# mainboard.net
KiCad netlist of a schematic drawn in EAGLE
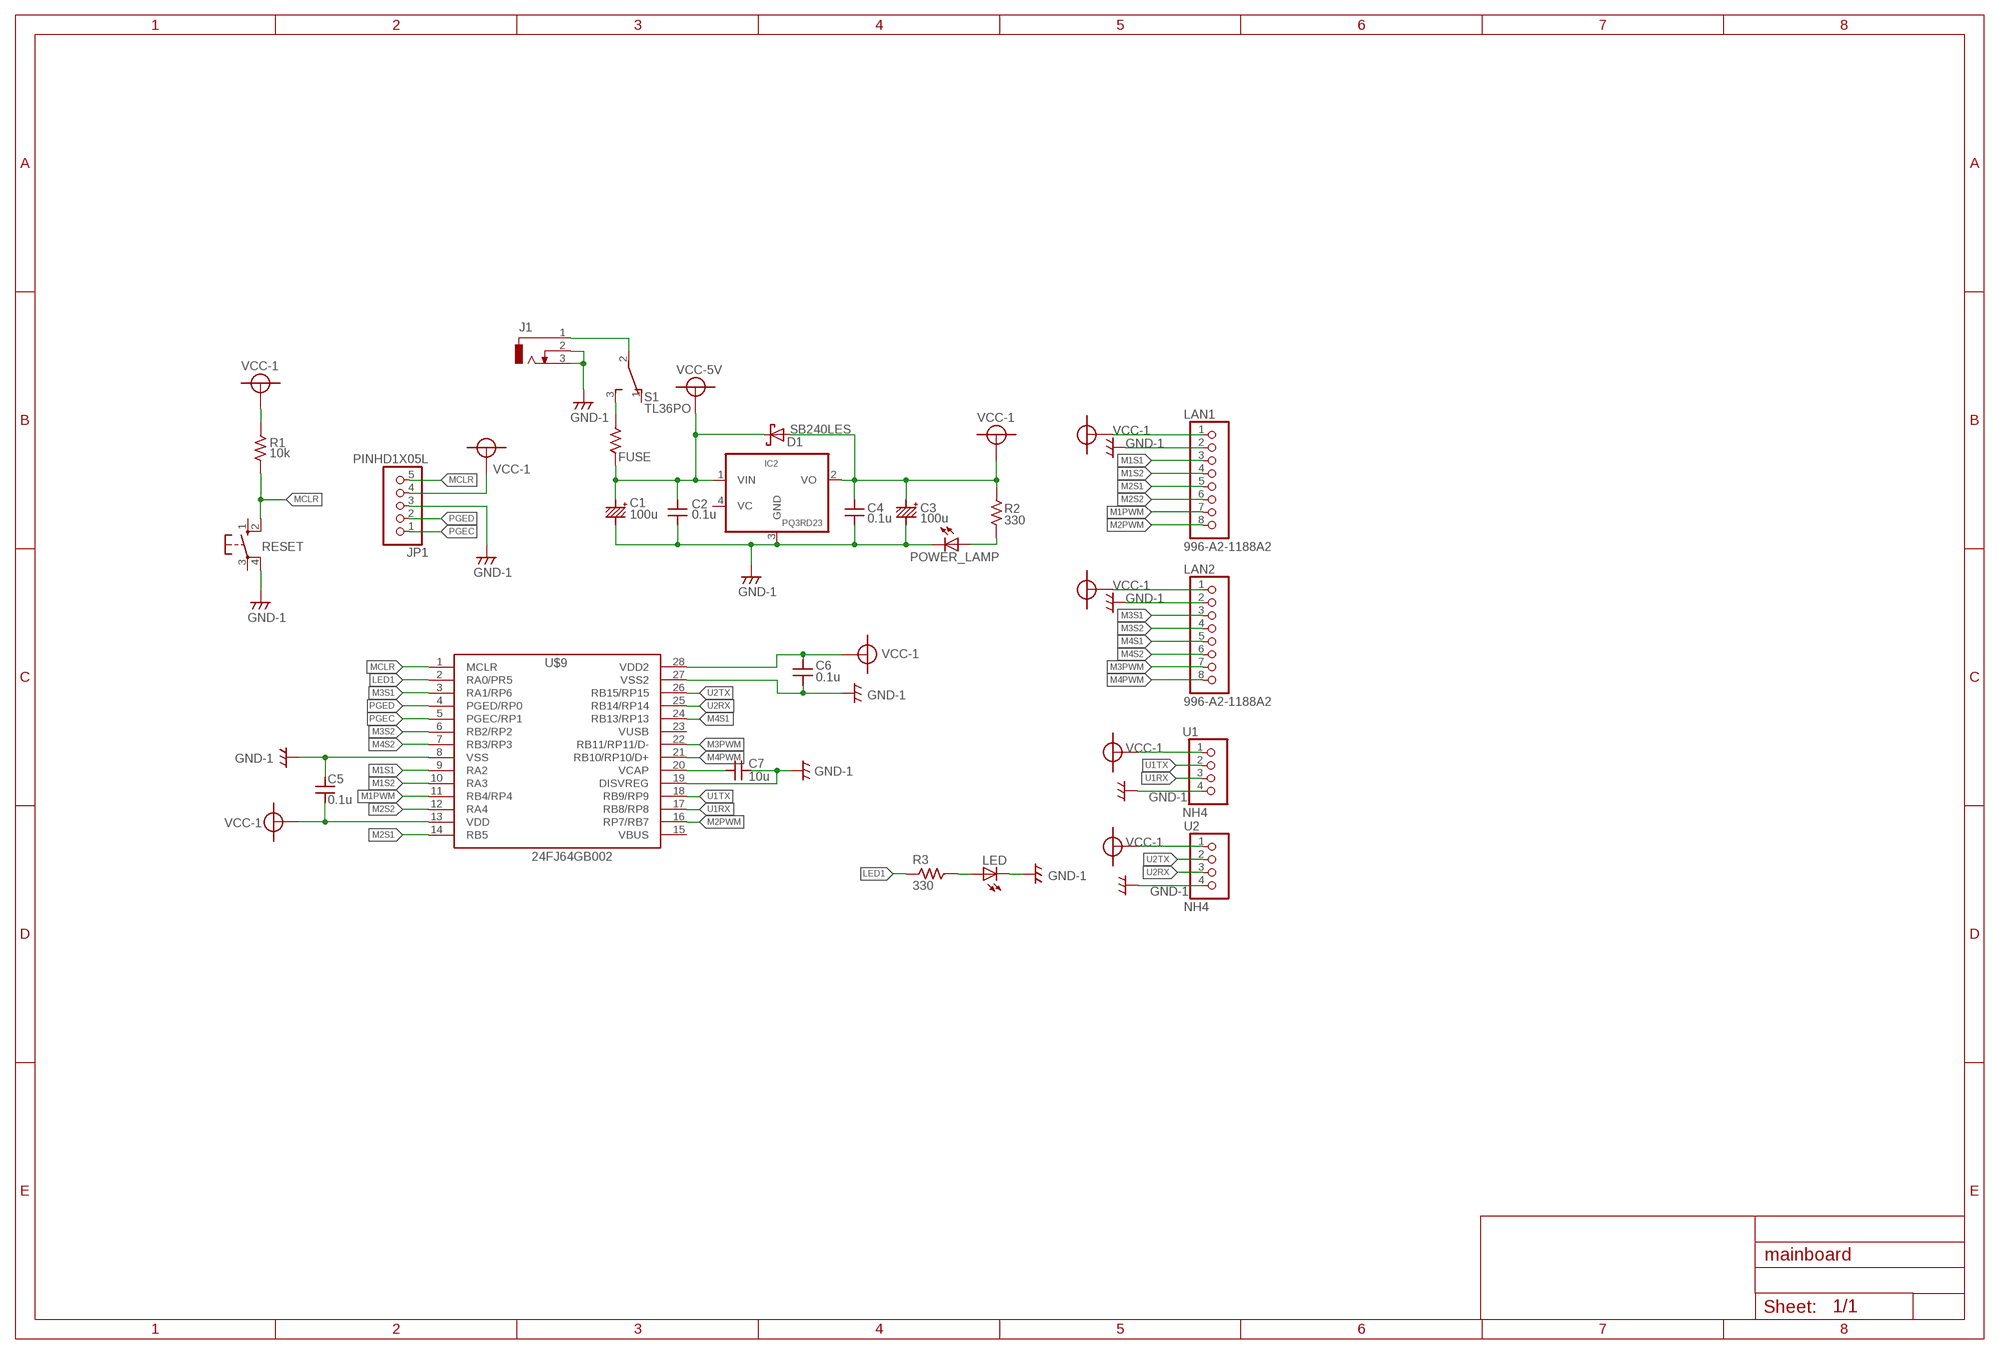
[diagram p0: schematic, sheet 1]

(export (version "E")
  (design (tool "Eeschema 10.0.6"))
  (components
    (comp (ref "C1")
      (value "100u")
      (footprint "eagle-import:CC_3")
      (libsource (lib "eagle-import") (part "C+25V100"))
    )
    (comp (ref "C2")
      (value "0.1u")
      (footprint "eagle-import:C_1")
      (libsource (lib "eagle-import") (part "CC2.54"))
    )
    (comp (ref "C3")
      (value "100u")
      (footprint "eagle-import:CC_3")
      (libsource (lib "eagle-import") (part "C+25V100"))
    )
    (comp (ref "C4")
      (value "0.1u")
      (footprint "eagle-import:C_1")
      (libsource (lib "eagle-import") (part "CC2.54"))
    )
    (comp (ref "C5")
      (value "0.1u")
      (footprint "eagle-import:C_1")
      (libsource (lib "eagle-import") (part "CC2.54"))
    )
    (comp (ref "C6")
      (value "0.1u")
      (footprint "eagle-import:C_1")
      (libsource (lib "eagle-import") (part "CC2.54"))
    )
    (comp (ref "C7")
      (value "10u")
      (footprint "eagle-import:C_1")
      (libsource (lib "eagle-import") (part "CC2.54"))
    )
    (comp (ref "D1")
      (value "SB240LES")
      (footprint "eagle-import:DO35-7")
      (libsource (lib "eagle-import") (part "SB240LES"))
    )
    (comp (ref "FUSE")
      (value "R3216(1206)")
      (footprint "eagle-import:C3216")
      (libsource (lib "eagle-import") (part "R3216(1206)"))
    )
    (comp (ref "IC2")
      (value "PQ3RD23")
      (footprint "eagle-import:TO220BV-4")
      (libsource (lib "eagle-import") (part "PQ3RD23"))
    )
    (comp (ref "J1")
      (value "DCJ0303")
      (footprint "eagle-import:DCJ0303")
      (libsource (lib "eagle-import") (part "DCJ0303"))
    )
    (comp (ref "JP1")
      (value "PINHD1X05L")
      (footprint "eagle-import:1X05L")
      (libsource (lib "eagle-import") (part "PINHD1X05L"))
    )
    (comp (ref "LAN1")
      (value "996-A2-1188A2")
      (footprint "eagle-import:996-A2-1188A2")
      (libsource (lib "eagle-import") (part "996-A2-1188A2"))
    )
    (comp (ref "LAN2")
      (value "996-A2-1188A2")
      (footprint "eagle-import:996-A2-1188A2")
      (libsource (lib "eagle-import") (part "996-A2-1188A2"))
    )
    (comp (ref "LED")
      (value "LED\"\"")
      (footprint "eagle-import:LED5MM")
      (libsource (lib "eagle-import") (part "LED{dblquote}{dblquote}"))
    )
    (comp (ref "POWER_LAMP")
      (value "LED\"\"")
      (footprint "eagle-import:LED5MM")
      (libsource (lib "eagle-import") (part "LED{dblquote}{dblquote}"))
    )
    (comp (ref "R1")
      (value "10k")
      (footprint "eagle-import:R_1_4W")
      (libsource (lib "eagle-import") (part "R1/4W"))
    )
    (comp (ref "R2")
      (value "330")
      (footprint "eagle-import:R_1_4W")
      (libsource (lib "eagle-import") (part "R1/4W"))
    )
    (comp (ref "R3")
      (value "330")
      (footprint "eagle-import:R_1_4W")
      (libsource (lib "eagle-import") (part "R1/4W"))
    )
    (comp (ref "RESET")
      (value "10-XX")
      (footprint "eagle-import:B3F-10XX")
      (fields (field (name "MPN") "B3F-1000"))
      (libsource (lib "eagle-import") (part "10-XX"))
    )
    (comp (ref "S1")
      (value "TL36PO")
      (footprint "eagle-import:TL3XPO")
      (libsource (lib "eagle-import") (part "TL36PO"))
    )
    (comp (ref "U$9")
      (value "24FJ64GB002")
      (footprint "eagle-import:DIL28-3")
      (libsource (lib "eagle-import") (part "24FJ64GB002"))
    )
    (comp (ref "U1")
      (value "NH4")
      (footprint "eagle-import:NH4")
      (libsource (lib "eagle-import") (part "NH4"))
    )
    (comp (ref "U2")
      (value "NH4")
      (footprint "eagle-import:NH4")
      (libsource (lib "eagle-import") (part "NH4"))
    )
  )
  (nets
    (net (code "1") (name "GND-1") (class "Default")
      (node (ref "C1") (pin "-") (pinfunction "P$2-_-") (pintype "passive"))
      (node (ref "C2") (pin "P$2") (pinfunction "P$2_P$2") (pintype "passive"))
      (node (ref "C3") (pin "-") (pinfunction "P$2-_-") (pintype "passive"))
      (node (ref "C4") (pin "P$2") (pinfunction "P$2_P$2") (pintype "passive"))
      (node (ref "C5") (pin "P$1") (pinfunction "P$1_P$1") (pintype "passive"))
      (node (ref "C6") (pin "P$2") (pinfunction "P$2_P$2") (pintype "passive"))
      (node (ref "C7") (pin "P$2") (pinfunction "P$2_P$2") (pintype "passive"))
      (node (ref "IC2") (pin "3") (pinfunction "GND_3") (pintype "bidirectional"))
      (node (ref "J1") (pin "2") (pinfunction "2_2") (pintype "passive"))
      (node (ref "J1") (pin "3") (pinfunction "3_3") (pintype "passive"))
      (node (ref "JP1") (pin "3") (pinfunction "P$3_3") (pintype "bidirectional"))
      (node (ref "LAN1") (pin "2") (pinfunction "P$2_2") (pintype "bidirectional"))
      (node (ref "LAN2") (pin "2") (pinfunction "P$2_2") (pintype "bidirectional"))
      (node (ref "LED") (pin "K") (pinfunction "C_K") (pintype "passive"))
      (node (ref "POWER_LAMP") (pin "K") (pinfunction "C_K") (pintype "passive"))
      (node (ref "RESET") (pin "4") (pinfunction "P1_4") (pintype "passive"))
      (node (ref "U$9") (pin "19") (pinfunction "DISVREG_19") (pintype "bidirectional"))
      (node (ref "U$9") (pin "27") (pinfunction "VSS2_27") (pintype "bidirectional"))
      (node (ref "U$9") (pin "8") (pinfunction "VSS_8") (pintype "bidirectional"))
      (node (ref "U1") (pin "4") (pinfunction "P$4_4") (pintype "bidirectional"))
      (node (ref "U2") (pin "4") (pinfunction "P$4_4") (pintype "bidirectional"))
    )
    (net (code "2") (name "LED1") (class "Default")
      (node (ref "R3") (pin "P$1") (pinfunction "P$1_P$1") (pintype "passive"))
      (node (ref "U$9") (pin "2") (pinfunction "RA0/PR5_2") (pintype "bidirectional"))
    )
    (net (code "3") (name "M1PWM") (class "Default")
      (node (ref "LAN1") (pin "7") (pinfunction "P$7_7") (pintype "bidirectional"))
      (node (ref "U$9") (pin "11") (pinfunction "RB4/RP4_11") (pintype "bidirectional"))
    )
    (net (code "4") (name "M1S1") (class "Default")
      (node (ref "LAN1") (pin "3") (pinfunction "P$3_3") (pintype "bidirectional"))
      (node (ref "U$9") (pin "9") (pinfunction "RA2_9") (pintype "bidirectional"))
    )
    (net (code "5") (name "M1S2") (class "Default")
      (node (ref "LAN1") (pin "4") (pinfunction "P$4_4") (pintype "bidirectional"))
      (node (ref "U$9") (pin "10") (pinfunction "RA3_10") (pintype "bidirectional"))
    )
    (net (code "6") (name "M2PWM") (class "Default")
      (node (ref "LAN1") (pin "8") (pinfunction "P$8_8") (pintype "bidirectional"))
      (node (ref "U$9") (pin "16") (pinfunction "RP7/RB7_16") (pintype "bidirectional"))
    )
    (net (code "7") (name "M2S1") (class "Default")
      (node (ref "LAN1") (pin "5") (pinfunction "P$5_5") (pintype "bidirectional"))
      (node (ref "U$9") (pin "14") (pinfunction "RB5_14") (pintype "bidirectional"))
    )
    (net (code "8") (name "M2S2") (class "Default")
      (node (ref "LAN1") (pin "6") (pinfunction "P$6_6") (pintype "bidirectional"))
      (node (ref "U$9") (pin "12") (pinfunction "RA4_12") (pintype "bidirectional"))
    )
    (net (code "9") (name "M3PWM") (class "Default")
      (node (ref "LAN2") (pin "7") (pinfunction "P$7_7") (pintype "bidirectional"))
      (node (ref "U$9") (pin "22") (pinfunction "RB11/RP11/D-_22") (pintype "bidirectional"))
    )
    (net (code "10") (name "M3S1") (class "Default")
      (node (ref "LAN2") (pin "3") (pinfunction "P$3_3") (pintype "bidirectional"))
      (node (ref "U$9") (pin "3") (pinfunction "RA1/RP6_3") (pintype "bidirectional"))
    )
    (net (code "11") (name "M3S2") (class "Default")
      (node (ref "LAN2") (pin "4") (pinfunction "P$4_4") (pintype "bidirectional"))
      (node (ref "U$9") (pin "6") (pinfunction "RB2/RP2_6") (pintype "bidirectional"))
    )
    (net (code "12") (name "M4PWM") (class "Default")
      (node (ref "LAN2") (pin "8") (pinfunction "P$8_8") (pintype "bidirectional"))
      (node (ref "U$9") (pin "21") (pinfunction "RB10/RP10/D+_21") (pintype "bidirectional"))
    )
    (net (code "13") (name "M4S1") (class "Default")
      (node (ref "LAN2") (pin "5") (pinfunction "P$5_5") (pintype "bidirectional"))
      (node (ref "U$9") (pin "24") (pinfunction "RB13/RP13_24") (pintype "bidirectional"))
    )
    (net (code "14") (name "M4S2") (class "Default")
      (node (ref "LAN2") (pin "6") (pinfunction "P$6_6") (pintype "bidirectional"))
      (node (ref "U$9") (pin "7") (pinfunction "RB3/RP3_7") (pintype "bidirectional"))
    )
    (net (code "15") (name "MCLR") (class "Default")
      (node (ref "JP1") (pin "5") (pinfunction "P$5_5") (pintype "bidirectional"))
      (node (ref "R1") (pin "P$1") (pinfunction "P$1_P$1") (pintype "passive"))
      (node (ref "RESET") (pin "2") (pinfunction "S1_2") (pintype "passive"))
      (node (ref "U$9") (pin "1") (pinfunction "MCLR_1") (pintype "bidirectional"))
    )
    (net (code "16") (name "Net-(FUSE-P$2)") (class "Default")
      (node (ref "FUSE") (pin "2") (pinfunction "P$2_2") (pintype "passive"))
      (node (ref "S1") (pin "3") (pinfunction "S_3") (pintype "passive"))
    )
    (net (code "17") (name "Net-(LED-PadA)") (class "Default")
      (node (ref "LED") (pin "A") (pinfunction "A_A") (pintype "passive"))
      (node (ref "R3") (pin "P$2") (pinfunction "P$2_P$2") (pintype "passive"))
    )
    (net (code "18") (name "Net-(POWER_LAMP-PadA)") (class "Default")
      (node (ref "POWER_LAMP") (pin "A") (pinfunction "A_A") (pintype "passive"))
      (node (ref "R2") (pin "P$1") (pinfunction "P$1_P$1") (pintype "passive"))
    )
    (net (code "19") (name "Net-(S1-P)") (class "Default")
      (node (ref "J1") (pin "1") (pinfunction "1_1") (pintype "passive"))
      (node (ref "S1") (pin "2") (pinfunction "P_2") (pintype "passive"))
    )
    (net (code "20") (name "Net-(U$9-VCAP)") (class "Default")
      (node (ref "C7") (pin "P$1") (pinfunction "P$1_P$1") (pintype "passive"))
      (node (ref "U$9") (pin "20") (pinfunction "VCAP_20") (pintype "bidirectional"))
    )
    (net (code "21") (name "PGEC") (class "Default")
      (node (ref "JP1") (pin "1") (pinfunction "P$1_1") (pintype "bidirectional"))
      (node (ref "U$9") (pin "5") (pinfunction "PGEC/RP1_5") (pintype "bidirectional"))
    )
    (net (code "22") (name "PGED") (class "Default")
      (node (ref "JP1") (pin "2") (pinfunction "P$2_2") (pintype "bidirectional"))
      (node (ref "U$9") (pin "4") (pinfunction "PGED/RP0_4") (pintype "bidirectional"))
    )
    (net (code "23") (name "U1RX") (class "Default")
      (node (ref "U$9") (pin "17") (pinfunction "RB8/RP8_17") (pintype "bidirectional"))
      (node (ref "U1") (pin "3") (pinfunction "P$3_3") (pintype "bidirectional"))
    )
    (net (code "24") (name "U1TX") (class "Default")
      (node (ref "U$9") (pin "18") (pinfunction "RB9/RP9_18") (pintype "bidirectional"))
      (node (ref "U1") (pin "2") (pinfunction "P$2_2") (pintype "bidirectional"))
    )
    (net (code "25") (name "U2RX") (class "Default")
      (node (ref "U$9") (pin "25") (pinfunction "RB14/RP14_25") (pintype "bidirectional"))
      (node (ref "U2") (pin "3") (pinfunction "P$3_3") (pintype "bidirectional"))
    )
    (net (code "26") (name "U2TX") (class "Default")
      (node (ref "U$9") (pin "26") (pinfunction "RB15/RP15_26") (pintype "bidirectional"))
      (node (ref "U2") (pin "2") (pinfunction "P$2_2") (pintype "bidirectional"))
    )
    (net (code "27") (name "VCC-1") (class "Default")
      (node (ref "C3") (pin "+") (pinfunction "P$1+_+") (pintype "passive"))
      (node (ref "C4") (pin "P$1") (pinfunction "P$1_P$1") (pintype "passive"))
      (node (ref "C5") (pin "P$2") (pinfunction "P$2_P$2") (pintype "passive"))
      (node (ref "C6") (pin "P$1") (pinfunction "P$1_P$1") (pintype "passive"))
      (node (ref "D1") (pin "A") (pinfunction "A_A") (pintype "passive"))
      (node (ref "IC2") (pin "2") (pinfunction "VO_2") (pintype "bidirectional"))
      (node (ref "JP1") (pin "4") (pinfunction "P$4_4") (pintype "bidirectional"))
      (node (ref "LAN1") (pin "1") (pinfunction "P$1_1") (pintype "bidirectional"))
      (node (ref "LAN2") (pin "1") (pinfunction "P$1_1") (pintype "bidirectional"))
      (node (ref "R1") (pin "P$2") (pinfunction "P$2_P$2") (pintype "passive"))
      (node (ref "R2") (pin "P$2") (pinfunction "P$2_P$2") (pintype "passive"))
      (node (ref "U$9") (pin "13") (pinfunction "VDD_13") (pintype "bidirectional"))
      (node (ref "U$9") (pin "28") (pinfunction "VDD2_28") (pintype "bidirectional"))
      (node (ref "U1") (pin "1") (pinfunction "P$1_1") (pintype "bidirectional"))
      (node (ref "U2") (pin "1") (pinfunction "P$1_1") (pintype "bidirectional"))
    )
    (net (code "28") (name "VCC-5V") (class "Default")
      (node (ref "C1") (pin "+") (pinfunction "P$1+_+") (pintype "passive"))
      (node (ref "C2") (pin "P$1") (pinfunction "P$1_P$1") (pintype "passive"))
      (node (ref "D1") (pin "C") (pinfunction "C_C") (pintype "passive"))
      (node (ref "FUSE") (pin "1") (pinfunction "P$1_1") (pintype "passive"))
      (node (ref "IC2") (pin "1") (pinfunction "VIN_1") (pintype "bidirectional"))
    )
    (net (code "29") (name "unconnected-(IC2-VC-Pad4)") (class "Default")
      (node (ref "IC2") (pin "4") (pinfunction "VC_4") (pintype "bidirectional"))
    )
    (net (code "30") (name "unconnected-(RESET-P-Pad3)") (class "Default")
      (node (ref "RESET") (pin "3") (pinfunction "P_3") (pintype "passive"))
    )
    (net (code "31") (name "unconnected-(RESET-S-Pad1)") (class "Default")
      (node (ref "RESET") (pin "1") (pinfunction "S_1") (pintype "passive"))
    )
    (net (code "32") (name "unconnected-(S1-O-Pad1)") (class "Default")
      (node (ref "S1") (pin "1") (pinfunction "O_1") (pintype "passive"))
    )
    (net (code "33") (name "unconnected-(U$9-VBUS-Pad15)") (class "Default")
      (node (ref "U$9") (pin "15") (pinfunction "VBUS_15") (pintype "bidirectional"))
    )
    (net (code "34") (name "unconnected-(U$9-VUSB-Pad23)") (class "Default")
      (node (ref "U$9") (pin "23") (pinfunction "VUSB_23") (pintype "bidirectional"))
    )
  )
)
